# sensors-ssm.net
KiCad netlist of a schematic drawn in Altium Designer
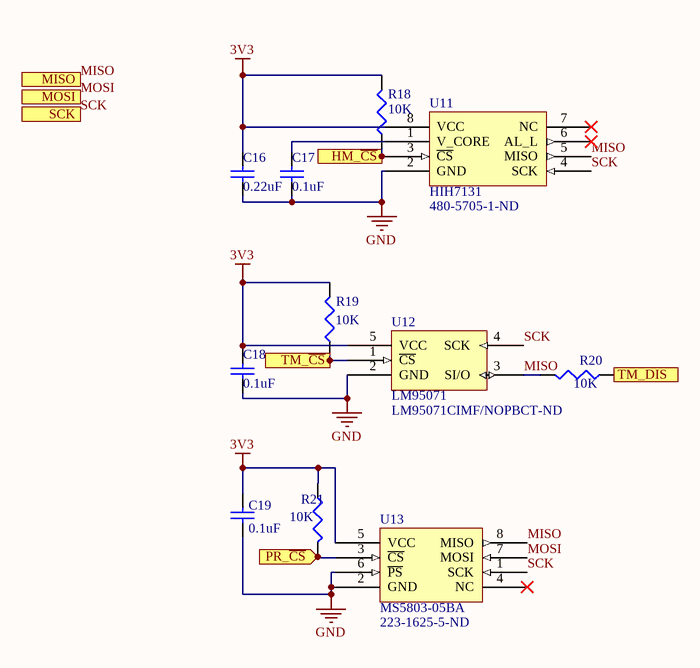
[diagram p0: sensors-ssm.SchDoc]

(export (version "E")
  (design (tool "Eeschema 10.0.6"))
  (components
    (comp (ref "C16")
      (value "0.22uF")
      (footprint "C1206")
      (description "Capacitor (Semiconductor SIM Model)")
      (fields (field (name "Comment") "Cap Semi") (field (name "PUBLISHER") "Altium Limited"))
      (libsource (lib "Miscellaneous Devices") (part "Cap Semi"))
    )
    (comp (ref "C17")
      (value "0.1uF")
      (footprint "C1206")
      (description "Capacitor (Semiconductor SIM Model)")
      (fields (field (name "Comment") "Cap Semi") (field (name "PUBLISHER") "Altium Limited"))
      (libsource (lib "Miscellaneous Devices") (part "Cap Semi"))
    )
    (comp (ref "C18")
      (value "0.1uF")
      (footprint "C1206")
      (description "Capacitor (Semiconductor SIM Model)")
      (fields (field (name "Comment") "Cap Semi") (field (name "PUBLISHER") "Altium Limited"))
      (libsource (lib "Miscellaneous Devices") (part "Cap Semi"))
    )
    (comp (ref "C19")
      (value "0.1uF")
      (footprint "C1206")
      (description "Capacitor (Semiconductor SIM Model)")
      (fields (field (name "Comment") "Cap Semi") (field (name "PUBLISHER") "Altium Limited"))
      (libsource (lib "Miscellaneous Devices") (part "Cap Semi"))
    )
    (comp (ref "R18")
      (value "10K")
      (footprint "J1-0603")
      (description "Resistor")
      (fields (field (name "Comment") "Res3") (field (name "PUBLISHER") "Altium Limited"))
      (libsource (lib "Miscellaneous Devices") (part "Res3"))
    )
    (comp (ref "R19")
      (value "10K")
      (footprint "J1-0603")
      (description "Resistor")
      (fields (field (name "Comment") "Res3") (field (name "PUBLISHER") "Altium Limited"))
      (libsource (lib "Miscellaneous Devices") (part "Res3"))
    )
    (comp (ref "R20")
      (value "10K")
      (footprint "J1-0603")
      (description "Resistor")
      (fields (field (name "Comment") "Res3") (field (name "PUBLISHER") "Altium Limited"))
      (libsource (lib "Miscellaneous Devices") (part "Res3"))
    )
    (comp (ref "R21")
      (value "10K")
      (footprint "J1-0603")
      (description "Resistor")
      (fields (field (name "Comment") "Res3") (field (name "PUBLISHER") "Altium Limited"))
      (libsource (lib "Miscellaneous Devices") (part "Res3"))
    )
    (comp (ref "U11")
      (value "HIH7131")
      (footprint "SOIC127P500X600-8N")
      (fields (field (name "SUPPLIER PART NUMBER 1") "480-5705-1-ND"))
      (libsource (lib "PAY") (part "HIH7131"))
    )
    (comp (ref "U12")
      (value "LM95071")
      (footprint "SOT-23-5_95P290X160-5N")
      (description "13 bit plus sign digital temperature sensor. Nominal +/- 1 C accuracy from 0-70 C.")
      (fields (field (name "SUPPLIER PART NUMBER 1") "LM95071CIMF/NOPBCT-ND"))
      (libsource (lib "PAY") (part "LM95071"))
    )
    (comp (ref "U13")
      (value "MS5803-05BA")
      (footprint "MS5803-05BA_125P640x620-8N")
      (fields (field (name "SUPPLIER PART NUMBER 1") "223-1625-5-ND"))
      (libsource (lib "PAY") (part "MS5803-05BA"))
    )
  )
  (nets
    (net (code "1") (name "/HM_~{CS}") (class "Default")
      (node (ref "R18") (pin "1") (pinfunction "1_1") (pintype "passive"))
      (node (ref "U11") (pin "3") (pinfunction "~{CS}_3") (pintype "input"))
    )
    (net (code "2") (name "/MISO") (class "Default")
      (node (ref "R20") (pin "2") (pinfunction "2_2") (pintype "passive"))
      (node (ref "U11") (pin "5") (pinfunction "MISO_5") (pintype "output"))
      (node (ref "U12") (pin "3") (pinfunction "SI/O_3") (pintype "bidirectional"))
      (node (ref "U13") (pin "8") (pinfunction "MISO_8") (pintype "output"))
    )
    (net (code "3") (name "/MOSI") (class "Default")
      (node (ref "U13") (pin "7") (pinfunction "MOSI_7") (pintype "input"))
    )
    (net (code "4") (name "/PR_~{CS}") (class "Default")
      (node (ref "R21") (pin "2") (pinfunction "2_2") (pintype "passive"))
      (node (ref "U13") (pin "3") (pinfunction "~{CS}_3") (pintype "input"))
    )
    (net (code "5") (name "/SCK") (class "Default")
      (node (ref "U11") (pin "4") (pinfunction "SCK_4") (pintype "input"))
      (node (ref "U12") (pin "4") (pinfunction "SCK_4") (pintype "input"))
      (node (ref "U13") (pin "1") (pinfunction "SCK_1") (pintype "input"))
    )
    (net (code "6") (name "/TM_DIS") (class "Default")
      (node (ref "R20") (pin "1") (pinfunction "1_1") (pintype "passive"))
    )
    (net (code "7") (name "/TM_~{CS}") (class "Default")
      (node (ref "R19") (pin "1") (pinfunction "1_1") (pintype "passive"))
      (node (ref "U12") (pin "1") (pinfunction "~{CS}_1") (pintype "input"))
    )
    (net (code "8") (name "3V3") (class "Default")
      (node (ref "C16") (pin "2") (pinfunction "2_2") (pintype "passive"))
      (node (ref "C18") (pin "2") (pinfunction "2_2") (pintype "passive"))
      (node (ref "C19") (pin "2") (pinfunction "2_2") (pintype "passive"))
      (node (ref "R18") (pin "2") (pinfunction "2_2") (pintype "passive"))
      (node (ref "R19") (pin "2") (pinfunction "2_2") (pintype "passive"))
      (node (ref "R21") (pin "1") (pinfunction "1_1") (pintype "passive"))
      (node (ref "U11") (pin "8") (pinfunction "VCC_8") (pintype "power_in"))
      (node (ref "U12") (pin "5") (pinfunction "VCC_5") (pintype "power_in"))
      (node (ref "U13") (pin "5") (pinfunction "VCC_5") (pintype "power_in"))
    )
    (net (code "9") (name "GND") (class "Default")
      (node (ref "C16") (pin "1") (pinfunction "1_1") (pintype "passive"))
      (node (ref "C17") (pin "1") (pinfunction "1_1") (pintype "passive"))
      (node (ref "C18") (pin "1") (pinfunction "1_1") (pintype "passive"))
      (node (ref "C19") (pin "1") (pinfunction "1_1") (pintype "passive"))
      (node (ref "U11") (pin "2") (pinfunction "GND_2") (pintype "power_in"))
      (node (ref "U12") (pin "2") (pinfunction "GND_2") (pintype "power_in"))
      (node (ref "U13") (pin "2") (pinfunction "GND_2") (pintype "power_in"))
      (node (ref "U13") (pin "6") (pinfunction "~{PS}_6") (pintype "input"))
    )
    (net (code "10") (name "Net-(U11-V_CORE)") (class "Default")
      (node (ref "C17") (pin "2") (pinfunction "2_2") (pintype "passive"))
      (node (ref "U11") (pin "1") (pinfunction "V_CORE_1") (pintype "power_in"))
    )
    (net (code "11") (name "unconnected-(U11-AL_L-Pad6)") (class "Default")
      (node (ref "U11") (pin "6") (pinfunction "AL_L_6") (pintype "output+no_connect"))
    )
    (net (code "12") (name "unconnected-(U11-NC-Pad7)") (class "Default")
      (node (ref "U11") (pin "7") (pinfunction "NC_7") (pintype "passive+no_connect"))
    )
    (net (code "13") (name "unconnected-(U13-NC-Pad4)") (class "Default")
      (node (ref "U13") (pin "4") (pinfunction "NC_4") (pintype "passive+no_connect"))
    )
  )
)
